# Genus_MainBoard_Dev_v_1_0.net
KiCad netlist of a schematic drawn in EAGLE
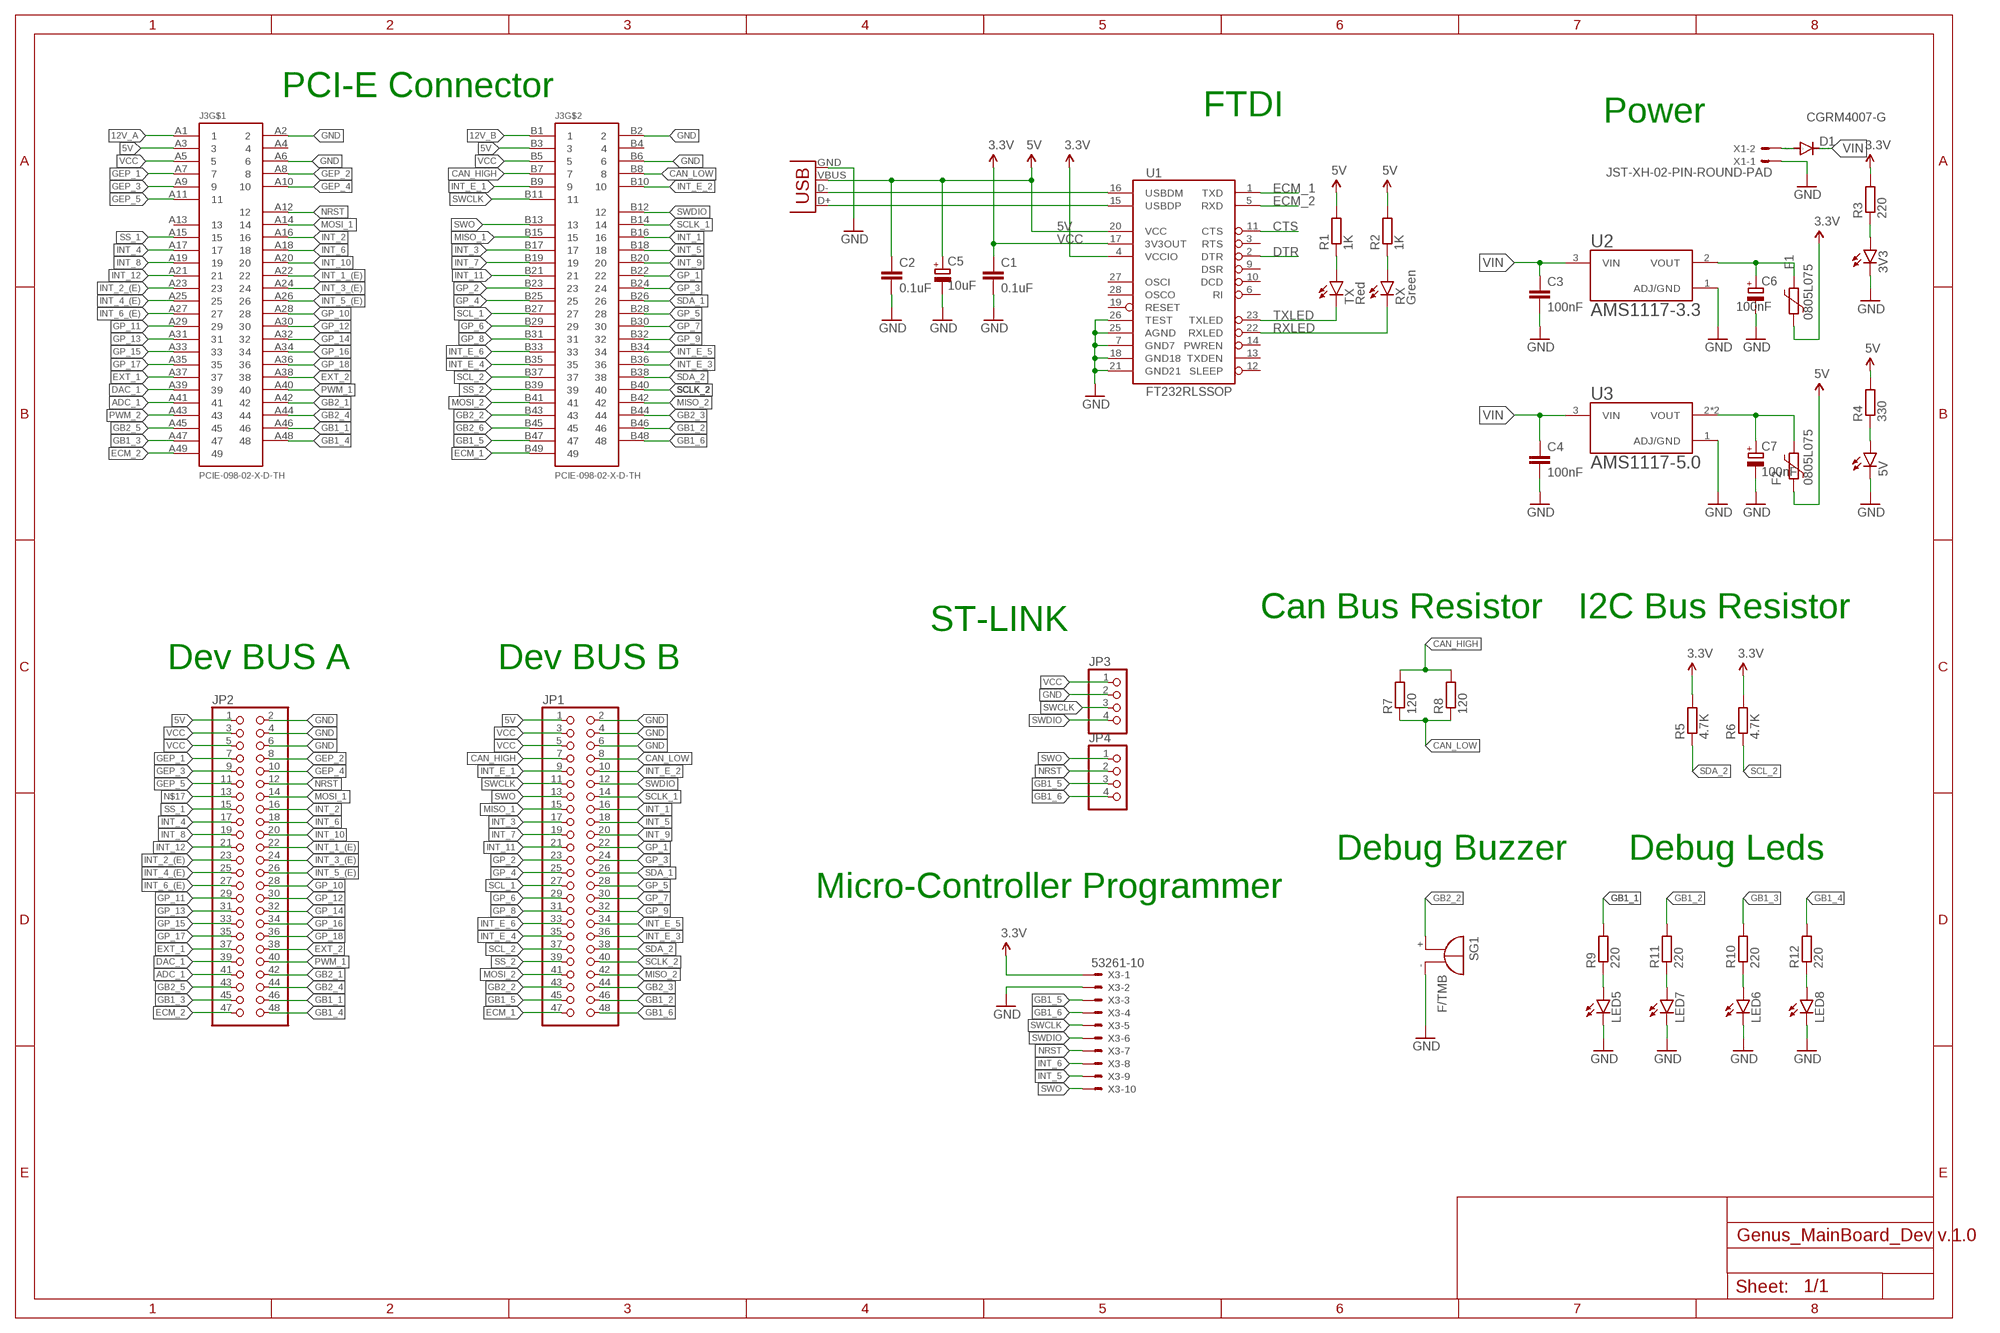
[diagram p0: schematic, sheet 1]

(export (version "E")
  (design (tool "Eeschema 10.0.6"))
  (components
    (comp (ref "3V3")
      (value "LEDCHIPLED_0805")
      (footprint "eagle-import:CHIPLED_0805")
      (libsource (lib "eagle-import") (part "LEDCHIPLED_0805"))
    )
    (comp (ref "5V")
      (value "LEDCHIPLED_0805")
      (footprint "eagle-import:CHIPLED_0805")
      (libsource (lib "eagle-import") (part "LEDCHIPLED_0805"))
    )
    (comp (ref "C1")
      (value "0.1uF")
      (footprint "eagle-import:C0805")
      (libsource (lib "eagle-import") (part "C-EUC0805"))
    )
    (comp (ref "C2")
      (value "0.1uF")
      (footprint "eagle-import:C0805")
      (libsource (lib "eagle-import") (part "C-EUC0805"))
    )
    (comp (ref "C3")
      (value "100nF")
      (footprint "eagle-import:C0805")
      (libsource (lib "eagle-import") (part "C-EUC0805"))
    )
    (comp (ref "C4")
      (value "100nF")
      (footprint "eagle-import:C0805")
      (libsource (lib "eagle-import") (part "C-EUC0805"))
    )
    (comp (ref "C5")
      (value "10uF")
      (footprint "eagle-import:PANASONIC_B")
      (libsource (lib "eagle-import") (part "CPOL-EUB"))
    )
    (comp (ref "C6")
      (value "100nF")
      (footprint "eagle-import:PANASONIC_B")
      (libsource (lib "eagle-import") (part "CPOL-EUB"))
    )
    (comp (ref "C7")
      (value "100nF")
      (footprint "eagle-import:PANASONIC_B")
      (libsource (lib "eagle-import") (part "CPOL-EUB"))
    )
    (comp (ref "D1")
      (value "CGRM4007-G")
      (footprint "eagle-import:SOD-123_MINI-SMA")
      (libsource (lib "eagle-import") (part "CGRM400-G7"))
    )
    (comp (ref "F1")
      (value "0805L075")
      (footprint "eagle-import:0805L")
      (fields (field (name "MF") "Littelfuse"))
      (libsource (lib "eagle-import") (part "?0805L075"))
    )
    (comp (ref "F2")
      (value "0805L075")
      (footprint "eagle-import:0805L")
      (fields (field (name "MF") "Littelfuse"))
      (libsource (lib "eagle-import") (part "?0805L075"))
    )
    (comp (ref "J3")
      (value "PCIE-098-02-X-D-TH")
      (footprint "eagle-import:PCIE-098-02-X-D-TH")
      (fields (field (name "MF") "Samtec") (field (name "MP") "PCIE-098-02-F-D-TH"))
      (libsource (lib "eagle-import") (part "PCIE-098-02-X-D-TH"))
    )
    (comp (ref "JP1")
      (value "PINHD-2X24")
      (footprint "eagle-import:2X24")
      (libsource (lib "eagle-import") (part "PINHD-2X24"))
    )
    (comp (ref "JP2")
      (value "PINHD-2X24")
      (footprint "eagle-import:2X24")
      (libsource (lib "eagle-import") (part "PINHD-2X24"))
    )
    (comp (ref "JP3")
      (value "PINHD-1X4")
      (footprint "eagle-import:1X04")
      (libsource (lib "eagle-import") (part "PINHD-1X4"))
    )
    (comp (ref "JP4")
      (value "PINHD-1X4")
      (footprint "eagle-import:1X04")
      (libsource (lib "eagle-import") (part "PINHD-1X4"))
    )
    (comp (ref "LED5")
      (value "LEDCHIPLED_0805")
      (footprint "eagle-import:CHIPLED_0805")
      (libsource (lib "eagle-import") (part "LEDCHIPLED_0805"))
    )
    (comp (ref "LED6")
      (value "LEDCHIPLED_0805")
      (footprint "eagle-import:CHIPLED_0805")
      (libsource (lib "eagle-import") (part "LEDCHIPLED_0805"))
    )
    (comp (ref "LED7")
      (value "LEDCHIPLED_0805")
      (footprint "eagle-import:CHIPLED_0805")
      (libsource (lib "eagle-import") (part "LEDCHIPLED_0805"))
    )
    (comp (ref "LED8")
      (value "LEDCHIPLED_0805")
      (footprint "eagle-import:CHIPLED_0805")
      (libsource (lib "eagle-import") (part "LEDCHIPLED_0805"))
    )
    (comp (ref "R1")
      (value "1K")
      (footprint "eagle-import:R0805")
      (libsource (lib "eagle-import") (part "R-EU_R0805"))
    )
    (comp (ref "R2")
      (value "1K")
      (footprint "eagle-import:R0805")
      (libsource (lib "eagle-import") (part "R-EU_R0805"))
    )
    (comp (ref "R3")
      (value "220")
      (footprint "eagle-import:R0805")
      (libsource (lib "eagle-import") (part "R-EU_R0805"))
    )
    (comp (ref "R4")
      (value "330")
      (footprint "eagle-import:R0805")
      (libsource (lib "eagle-import") (part "R-EU_R0805"))
    )
    (comp (ref "R5")
      (value "4.7K")
      (footprint "eagle-import:R0805")
      (libsource (lib "eagle-import") (part "R-EU_R0805"))
    )
    (comp (ref "R6")
      (value "4.7K")
      (footprint "eagle-import:R0805")
      (libsource (lib "eagle-import") (part "R-EU_R0805"))
    )
    (comp (ref "R7")
      (value "120")
      (footprint "eagle-import:R0805")
      (libsource (lib "eagle-import") (part "R-EU_R0805"))
    )
    (comp (ref "R8")
      (value "120")
      (footprint "eagle-import:R0805")
      (libsource (lib "eagle-import") (part "R-EU_R0805"))
    )
    (comp (ref "R9")
      (value "220")
      (footprint "eagle-import:R0805")
      (libsource (lib "eagle-import") (part "R-EU_R0805"))
    )
    (comp (ref "R10")
      (value "220")
      (footprint "eagle-import:R0805")
      (libsource (lib "eagle-import") (part "R-EU_R0805"))
    )
    (comp (ref "R11")
      (value "220")
      (footprint "eagle-import:R0805")
      (libsource (lib "eagle-import") (part "R-EU_R0805"))
    )
    (comp (ref "R12")
      (value "220")
      (footprint "eagle-import:R0805")
      (libsource (lib "eagle-import") (part "R-EU_R0805"))
    )
    (comp (ref "RX")
      (value "Green")
      (footprint "eagle-import:CHIPLED_0805")
      (libsource (lib "eagle-import") (part "LEDCHIPLED_0805"))
    )
    (comp (ref "SG1")
      (value "F/TMB")
      (footprint "eagle-import:F_TMB")
      (libsource (lib "eagle-import") (part "F/TMB"))
    )
    (comp (ref "TX")
      (value "Red")
      (footprint "eagle-import:CHIPLED_0805")
      (libsource (lib "eagle-import") (part "LEDCHIPLED_0805"))
    )
    (comp (ref "U1")
      (value "FT232RLSSOP")
      (footprint "eagle-import:SSOP28DB")
      (libsource (lib "eagle-import") (part "FT232RLSSOP"))
    )
    (comp (ref "U2")
      (value "AMS1117-3.3")
      (footprint "eagle-import:SOT229P700X180-4N")
      (fields (field (name "MF") "Advanced Monolithic Systems"))
      (libsource (lib "eagle-import") (part "AMS1117-3.3"))
    )
    (comp (ref "U3")
      (value "AMS1117-5.0")
      (footprint "eagle-import:SOT229P700X180-4N")
      (fields (field (name "MF") "ams"))
      (libsource (lib "eagle-import") (part "AMS1117-5.0"))
    )
    (comp (ref "X1")
      (value "JST-XH-02-PIN-ROUND-PAD")
      (footprint "eagle-import:JST-XH-02-PACKAGE-ROUND-PAD")
      (libsource (lib "eagle-import") (part "JST-XH-02-PIN-ROUND-PAD"))
    )
    (comp (ref "X2")
      (value "USB-SMD-NS")
      (footprint "eagle-import:USB-MINIB-NOSTOP")
      (libsource (lib "eagle-import") (part "USB-SMD-NS"))
    )
    (comp (ref "X3")
      (value "53261-10")
      (footprint "eagle-import:53261-10")
      (fields (field (name "MF") "MOLEX"))
      (libsource (lib "eagle-import") (part "53?-10261"))
    )
  )
  (nets
    (net (code "1") (name "/CTS") (class "Default")
      (node (ref "U1") (pin "11") (pinfunction "CTS_11") (pintype "input"))
    )
    (net (code "2") (name "/DTR") (class "Default")
      (node (ref "U1") (pin "2") (pinfunction "DTR_2") (pintype "output"))
    )
    (net (code "3") (name "/RXLED") (class "Default")
      (node (ref "RX") (pin "C") (pinfunction "C_C") (pintype "passive"))
      (node (ref "U1") (pin "22") (pinfunction "RXLED_22") (pintype "input"))
    )
    (net (code "4") (name "/TXLED") (class "Default")
      (node (ref "TX") (pin "C") (pinfunction "C_C") (pintype "passive"))
      (node (ref "U1") (pin "23") (pinfunction "TXLED_23") (pintype "input"))
    )
    (net (code "5") (name "5V") (class "Default")
      (node (ref "C2") (pin "1") (pinfunction "1_1") (pintype "passive"))
      (node (ref "C5") (pin "+") (pinfunction "+_+") (pintype "passive"))
      (node (ref "F2") (pin "2") (pinfunction "2_2") (pintype "passive"))
      (node (ref "J3") (pin "A3") (pinfunction "3_A3") (pintype "bidirectional"))
      (node (ref "J3") (pin "B3") (pinfunction "3_B3") (pintype "bidirectional"))
      (node (ref "JP1") (pin "1") (pinfunction "1_1") (pintype "passive"))
      (node (ref "JP2") (pin "1") (pinfunction "1_1") (pintype "passive"))
      (node (ref "R1") (pin "2") (pinfunction "2_2") (pintype "passive"))
      (node (ref "R2") (pin "2") (pinfunction "2_2") (pintype "passive"))
      (node (ref "R4") (pin "2") (pinfunction "2_2") (pintype "passive"))
      (node (ref "U1") (pin "20") (pinfunction "VCC_20") (pintype "power_in"))
      (node (ref "X2") (pin "VBUS") (pinfunction "VBUS_VBUS") (pintype "bidirectional"))
    )
    (net (code "6") (name "12V_A") (class "Default")
      (node (ref "J3") (pin "A1") (pinfunction "1_A1") (pintype "bidirectional"))
    )
    (net (code "7") (name "12V_B") (class "Default")
      (node (ref "J3") (pin "B1") (pinfunction "1_B1") (pintype "bidirectional"))
    )
    (net (code "8") (name "ADC_1") (class "Default")
      (node (ref "J3") (pin "A41") (pinfunction "41_A41") (pintype "bidirectional"))
      (node (ref "JP2") (pin "41") (pinfunction "41_41") (pintype "passive"))
    )
    (net (code "9") (name "CAN_HIGH") (class "Default")
      (node (ref "J3") (pin "B7") (pinfunction "7_B7") (pintype "bidirectional"))
      (node (ref "JP1") (pin "7") (pinfunction "7_7") (pintype "passive"))
      (node (ref "R7") (pin "2") (pinfunction "2_2") (pintype "passive"))
      (node (ref "R8") (pin "2") (pinfunction "2_2") (pintype "passive"))
    )
    (net (code "10") (name "CAN_LOW") (class "Default")
      (node (ref "J3") (pin "B8") (pinfunction "8_B8") (pintype "bidirectional"))
      (node (ref "JP1") (pin "8") (pinfunction "8_8") (pintype "passive"))
      (node (ref "R7") (pin "1") (pinfunction "1_1") (pintype "passive"))
      (node (ref "R8") (pin "1") (pinfunction "1_1") (pintype "passive"))
    )
    (net (code "11") (name "DAC_1") (class "Default")
      (node (ref "J3") (pin "A39") (pinfunction "39_A39") (pintype "bidirectional"))
      (node (ref "JP2") (pin "39") (pinfunction "39_39") (pintype "passive"))
    )
    (net (code "12") (name "ECM_1") (class "Default")
      (node (ref "J3") (pin "B49") (pinfunction "49_B49") (pintype "bidirectional"))
      (node (ref "JP1") (pin "47") (pinfunction "47_47") (pintype "passive"))
      (node (ref "U1") (pin "1") (pinfunction "TXD_1") (pintype "output"))
    )
    (net (code "13") (name "ECM_2") (class "Default")
      (node (ref "J3") (pin "A49") (pinfunction "49_A49") (pintype "bidirectional"))
      (node (ref "JP2") (pin "47") (pinfunction "47_47") (pintype "passive"))
      (node (ref "U1") (pin "5") (pinfunction "RXD_5") (pintype "input"))
    )
    (net (code "14") (name "EXT_1") (class "Default")
      (node (ref "J3") (pin "A37") (pinfunction "37_A37") (pintype "bidirectional"))
      (node (ref "JP2") (pin "37") (pinfunction "37_37") (pintype "passive"))
    )
    (net (code "15") (name "EXT_2") (class "Default")
      (node (ref "J3") (pin "A38") (pinfunction "38_A38") (pintype "bidirectional"))
      (node (ref "JP2") (pin "38") (pinfunction "38_38") (pintype "passive"))
    )
    (net (code "16") (name "GB1_1") (class "Default")
      (node (ref "J3") (pin "A46") (pinfunction "46_A46") (pintype "bidirectional"))
      (node (ref "JP2") (pin "46") (pinfunction "46_46") (pintype "passive"))
      (node (ref "R9") (pin "2") (pinfunction "2_2") (pintype "passive"))
    )
    (net (code "17") (name "GB1_2") (class "Default")
      (node (ref "J3") (pin "B46") (pinfunction "46_B46") (pintype "bidirectional"))
      (node (ref "JP1") (pin "46") (pinfunction "46_46") (pintype "passive"))
      (node (ref "R11") (pin "2") (pinfunction "2_2") (pintype "passive"))
    )
    (net (code "18") (name "GB1_3") (class "Default")
      (node (ref "J3") (pin "A47") (pinfunction "47_A47") (pintype "bidirectional"))
      (node (ref "JP2") (pin "45") (pinfunction "45_45") (pintype "passive"))
      (node (ref "R10") (pin "2") (pinfunction "2_2") (pintype "passive"))
    )
    (net (code "19") (name "GB1_4") (class "Default")
      (node (ref "J3") (pin "A48") (pinfunction "48_A48") (pintype "bidirectional"))
      (node (ref "JP2") (pin "48") (pinfunction "48_48") (pintype "passive"))
      (node (ref "R12") (pin "2") (pinfunction "2_2") (pintype "passive"))
    )
    (net (code "20") (name "GB1_5") (class "Default")
      (node (ref "J3") (pin "B47") (pinfunction "47_B47") (pintype "bidirectional"))
      (node (ref "JP1") (pin "45") (pinfunction "45_45") (pintype "passive"))
      (node (ref "JP4") (pin "3") (pinfunction "3_3") (pintype "passive"))
      (node (ref "X3") (pin "3") (pinfunction "S_3") (pintype "passive"))
    )
    (net (code "21") (name "GB1_6") (class "Default")
      (node (ref "J3") (pin "B48") (pinfunction "48_B48") (pintype "bidirectional"))
      (node (ref "JP1") (pin "48") (pinfunction "48_48") (pintype "passive"))
      (node (ref "JP4") (pin "4") (pinfunction "4_4") (pintype "passive"))
      (node (ref "X3") (pin "4") (pinfunction "S_4") (pintype "passive"))
    )
    (net (code "22") (name "GB2_1") (class "Default")
      (node (ref "J3") (pin "A42") (pinfunction "42_A42") (pintype "bidirectional"))
      (node (ref "JP2") (pin "42") (pinfunction "42_42") (pintype "passive"))
    )
    (net (code "23") (name "GB2_2") (class "Default")
      (node (ref "J3") (pin "B43") (pinfunction "43_B43") (pintype "bidirectional"))
      (node (ref "JP1") (pin "43") (pinfunction "43_43") (pintype "passive"))
      (node (ref "SG1") (pin "+") (pinfunction "+_+") (pintype "passive"))
    )
    (net (code "24") (name "GB2_3") (class "Default")
      (node (ref "J3") (pin "B44") (pinfunction "44_B44") (pintype "bidirectional"))
      (node (ref "JP1") (pin "44") (pinfunction "44_44") (pintype "passive"))
    )
    (net (code "25") (name "GB2_4") (class "Default")
      (node (ref "J3") (pin "A44") (pinfunction "44_A44") (pintype "bidirectional"))
      (node (ref "JP2") (pin "44") (pinfunction "44_44") (pintype "passive"))
    )
    (net (code "26") (name "GB2_5") (class "Default")
      (node (ref "J3") (pin "A45") (pinfunction "45_A45") (pintype "bidirectional"))
      (node (ref "JP2") (pin "43") (pinfunction "43_43") (pintype "passive"))
    )
    (net (code "27") (name "GB2_6") (class "Default")
      (node (ref "J3") (pin "B45") (pinfunction "45_B45") (pintype "bidirectional"))
    )
    (net (code "28") (name "GEP_1") (class "Default")
      (node (ref "J3") (pin "A7") (pinfunction "7_A7") (pintype "bidirectional"))
      (node (ref "JP2") (pin "7") (pinfunction "7_7") (pintype "passive"))
    )
    (net (code "29") (name "GEP_2") (class "Default")
      (node (ref "J3") (pin "A8") (pinfunction "8_A8") (pintype "bidirectional"))
      (node (ref "JP2") (pin "8") (pinfunction "8_8") (pintype "passive"))
    )
    (net (code "30") (name "GEP_3") (class "Default")
      (node (ref "J3") (pin "A9") (pinfunction "9_A9") (pintype "bidirectional"))
      (node (ref "JP2") (pin "9") (pinfunction "9_9") (pintype "passive"))
    )
    (net (code "31") (name "GEP_4") (class "Default")
      (node (ref "J3") (pin "A10") (pinfunction "10_A10") (pintype "bidirectional"))
      (node (ref "JP2") (pin "10") (pinfunction "10_10") (pintype "passive"))
    )
    (net (code "32") (name "GEP_5") (class "Default")
      (node (ref "J3") (pin "A11") (pinfunction "11_A11") (pintype "bidirectional"))
      (node (ref "JP2") (pin "11") (pinfunction "11_11") (pintype "passive"))
    )
    (net (code "33") (name "GND") (class "Default")
      (node (ref "3V3") (pin "C") (pinfunction "C_C") (pintype "passive"))
      (node (ref "5V") (pin "C") (pinfunction "C_C") (pintype "passive"))
      (node (ref "C1") (pin "2") (pinfunction "2_2") (pintype "passive"))
      (node (ref "C2") (pin "2") (pinfunction "2_2") (pintype "passive"))
      (node (ref "C3") (pin "2") (pinfunction "2_2") (pintype "passive"))
      (node (ref "C4") (pin "2") (pinfunction "2_2") (pintype "passive"))
      (node (ref "C5") (pin "-") (pinfunction "-_-") (pintype "passive"))
      (node (ref "C6") (pin "-") (pinfunction "-_-") (pintype "passive"))
      (node (ref "C7") (pin "-") (pinfunction "-_-") (pintype "passive"))
      (node (ref "J3") (pin "A2") (pinfunction "2_A2") (pintype "bidirectional"))
      (node (ref "J3") (pin "A6") (pinfunction "6_A6") (pintype "bidirectional"))
      (node (ref "J3") (pin "B2") (pinfunction "2_B2") (pintype "bidirectional"))
      (node (ref "J3") (pin "B6") (pinfunction "6_B6") (pintype "bidirectional"))
      (node (ref "JP1") (pin "2") (pinfunction "2_2") (pintype "passive"))
      (node (ref "JP1") (pin "4") (pinfunction "4_4") (pintype "passive"))
      (node (ref "JP1") (pin "6") (pinfunction "6_6") (pintype "passive"))
      (node (ref "JP2") (pin "2") (pinfunction "2_2") (pintype "passive"))
      (node (ref "JP2") (pin "4") (pinfunction "4_4") (pintype "passive"))
      (node (ref "JP2") (pin "6") (pinfunction "6_6") (pintype "passive"))
      (node (ref "JP3") (pin "2") (pinfunction "2_2") (pintype "passive"))
      (node (ref "LED5") (pin "C") (pinfunction "C_C") (pintype "passive"))
      (node (ref "LED6") (pin "C") (pinfunction "C_C") (pintype "passive"))
      (node (ref "LED7") (pin "C") (pinfunction "C_C") (pintype "passive"))
      (node (ref "LED8") (pin "C") (pinfunction "C_C") (pintype "passive"))
      (node (ref "SG1") (pin "-") (pinfunction "-_-") (pintype "passive"))
      (node (ref "U1") (pin "18") (pinfunction "GND18_18") (pintype "power_in"))
      (node (ref "U1") (pin "21") (pinfunction "GND21_21") (pintype "power_in"))
      (node (ref "U1") (pin "25") (pinfunction "AGND_25") (pintype "power_in"))
      (node (ref "U1") (pin "26") (pinfunction "TEST_26") (pintype "input"))
      (node (ref "U1") (pin "7") (pinfunction "GND7_7") (pintype "power_in"))
      (node (ref "U2") (pin "1") (pinfunction "ADJ/GND_1") (pintype "power_in"))
      (node (ref "U3") (pin "1") (pinfunction "ADJ/GND_1") (pintype "power_in"))
      (node (ref "X1") (pin "1") (pinfunction "S_1") (pintype "passive"))
      (node (ref "X2") (pin "GND") (pinfunction "GND_GND") (pintype "bidirectional"))
      (node (ref "X3") (pin "2") (pinfunction "S_2") (pintype "passive"))
    )
    (net (code "34") (name "GP_1") (class "Default")
      (node (ref "J3") (pin "B22") (pinfunction "22_B22") (pintype "bidirectional"))
      (node (ref "JP1") (pin "22") (pinfunction "22_22") (pintype "passive"))
    )
    (net (code "35") (name "GP_2") (class "Default")
      (node (ref "J3") (pin "B23") (pinfunction "23_B23") (pintype "bidirectional"))
      (node (ref "JP1") (pin "23") (pinfunction "23_23") (pintype "passive"))
    )
    (net (code "36") (name "GP_3") (class "Default")
      (node (ref "J3") (pin "B24") (pinfunction "24_B24") (pintype "bidirectional"))
      (node (ref "JP1") (pin "24") (pinfunction "24_24") (pintype "passive"))
    )
    (net (code "37") (name "GP_4") (class "Default")
      (node (ref "J3") (pin "B25") (pinfunction "25_B25") (pintype "bidirectional"))
      (node (ref "JP1") (pin "25") (pinfunction "25_25") (pintype "passive"))
    )
    (net (code "38") (name "GP_5") (class "Default")
      (node (ref "J3") (pin "B28") (pinfunction "28_B28") (pintype "bidirectional"))
      (node (ref "JP1") (pin "28") (pinfunction "28_28") (pintype "passive"))
    )
    (net (code "39") (name "GP_6") (class "Default")
      (node (ref "J3") (pin "B29") (pinfunction "29_B29") (pintype "bidirectional"))
      (node (ref "JP1") (pin "29") (pinfunction "29_29") (pintype "passive"))
    )
    (net (code "40") (name "GP_7") (class "Default")
      (node (ref "J3") (pin "B30") (pinfunction "30_B30") (pintype "bidirectional"))
      (node (ref "JP1") (pin "30") (pinfunction "30_30") (pintype "passive"))
    )
    (net (code "41") (name "GP_8") (class "Default")
      (node (ref "J3") (pin "B31") (pinfunction "31_B31") (pintype "bidirectional"))
      (node (ref "JP1") (pin "31") (pinfunction "31_31") (pintype "passive"))
    )
    (net (code "42") (name "GP_9") (class "Default")
      (node (ref "J3") (pin "B32") (pinfunction "32_B32") (pintype "bidirectional"))
      (node (ref "JP1") (pin "32") (pinfunction "32_32") (pintype "passive"))
    )
    (net (code "43") (name "GP_10") (class "Default")
      (node (ref "J3") (pin "A28") (pinfunction "28_A28") (pintype "bidirectional"))
      (node (ref "JP2") (pin "28") (pinfunction "28_28") (pintype "passive"))
    )
    (net (code "44") (name "GP_11") (class "Default")
      (node (ref "J3") (pin "A29") (pinfunction "29_A29") (pintype "bidirectional"))
      (node (ref "JP2") (pin "29") (pinfunction "29_29") (pintype "passive"))
    )
    (net (code "45") (name "GP_12") (class "Default")
      (node (ref "J3") (pin "A30") (pinfunction "30_A30") (pintype "bidirectional"))
      (node (ref "JP2") (pin "30") (pinfunction "30_30") (pintype "passive"))
    )
    (net (code "46") (name "GP_13") (class "Default")
      (node (ref "J3") (pin "A31") (pinfunction "31_A31") (pintype "bidirectional"))
      (node (ref "JP2") (pin "31") (pinfunction "31_31") (pintype "passive"))
    )
    (net (code "47") (name "GP_14") (class "Default")
      (node (ref "J3") (pin "A32") (pinfunction "32_A32") (pintype "bidirectional"))
      (node (ref "JP2") (pin "32") (pinfunction "32_32") (pintype "passive"))
    )
    (net (code "48") (name "GP_15") (class "Default")
      (node (ref "J3") (pin "A33") (pinfunction "33_A33") (pintype "bidirectional"))
      (node (ref "JP2") (pin "33") (pinfunction "33_33") (pintype "passive"))
    )
    (net (code "49") (name "GP_16") (class "Default")
      (node (ref "J3") (pin "A34") (pinfunction "34_A34") (pintype "bidirectional"))
      (node (ref "JP2") (pin "34") (pinfunction "34_34") (pintype "passive"))
    )
    (net (code "50") (name "GP_17") (class "Default")
      (node (ref "J3") (pin "A35") (pinfunction "35_A35") (pintype "bidirectional"))
      (node (ref "JP2") (pin "35") (pinfunction "35_35") (pintype "passive"))
    )
    (net (code "51") (name "GP_18") (class "Default")
      (node (ref "J3") (pin "A36") (pinfunction "36_A36") (pintype "bidirectional"))
      (node (ref "JP2") (pin "36") (pinfunction "36_36") (pintype "passive"))
    )
    (net (code "52") (name "INT_1") (class "Default")
      (node (ref "J3") (pin "B16") (pinfunction "16_B16") (pintype "bidirectional"))
      (node (ref "JP1") (pin "16") (pinfunction "16_16") (pintype "passive"))
    )
    (net (code "53") (name "INT_1_(E)") (class "Default")
      (node (ref "J3") (pin "A22") (pinfunction "22_A22") (pintype "bidirectional"))
      (node (ref "JP2") (pin "22") (pinfunction "22_22") (pintype "passive"))
    )
    (net (code "54") (name "INT_2") (class "Default")
      (node (ref "J3") (pin "A16") (pinfunction "16_A16") (pintype "bidirectional"))
      (node (ref "JP2") (pin "16") (pinfunction "16_16") (pintype "passive"))
    )
    (net (code "55") (name "INT_2_(E)") (class "Default")
      (node (ref "J3") (pin "A23") (pinfunction "23_A23") (pintype "bidirectional"))
      (node (ref "JP2") (pin "23") (pinfunction "23_23") (pintype "passive"))
    )
    (net (code "56") (name "INT_3") (class "Default")
      (node (ref "J3") (pin "B17") (pinfunction "17_B17") (pintype "bidirectional"))
      (node (ref "JP1") (pin "17") (pinfunction "17_17") (pintype "passive"))
    )
    (net (code "57") (name "INT_3_(E)") (class "Default")
      (node (ref "J3") (pin "A24") (pinfunction "24_A24") (pintype "bidirectional"))
      (node (ref "JP2") (pin "24") (pinfunction "24_24") (pintype "passive"))
    )
    (net (code "58") (name "INT_4") (class "Default")
      (node (ref "J3") (pin "A17") (pinfunction "17_A17") (pintype "bidirectional"))
      (node (ref "JP2") (pin "17") (pinfunction "17_17") (pintype "passive"))
    )
    (net (code "59") (name "INT_4_(E)") (class "Default")
      (node (ref "J3") (pin "A25") (pinfunction "25_A25") (pintype "bidirectional"))
      (node (ref "JP2") (pin "25") (pinfunction "25_25") (pintype "passive"))
    )
    (net (code "60") (name "INT_5") (class "Default")
      (node (ref "J3") (pin "B18") (pinfunction "18_B18") (pintype "bidirectional"))
      (node (ref "JP1") (pin "18") (pinfunction "18_18") (pintype "passive"))
      (node (ref "X3") (pin "9") (pinfunction "S_9") (pintype "passive"))
    )
    (net (code "61") (name "INT_5_(E)") (class "Default")
      (node (ref "J3") (pin "A26") (pinfunction "26_A26") (pintype "bidirectional"))
      (node (ref "JP2") (pin "26") (pinfunction "26_26") (pintype "passive"))
    )
    (net (code "62") (name "INT_6") (class "Default")
      (node (ref "J3") (pin "A18") (pinfunction "18_A18") (pintype "bidirectional"))
      (node (ref "JP2") (pin "18") (pinfunction "18_18") (pintype "passive"))
      (node (ref "X3") (pin "8") (pinfunction "S_8") (pintype "passive"))
    )
    (net (code "63") (name "INT_6_(E)") (class "Default")
      (node (ref "J3") (pin "A27") (pinfunction "27_A27") (pintype "bidirectional"))
      (node (ref "JP2") (pin "27") (pinfunction "27_27") (pintype "passive"))
    )
    (net (code "64") (name "INT_7") (class "Default")
      (node (ref "J3") (pin "B19") (pinfunction "19_B19") (pintype "bidirectional"))
      (node (ref "JP1") (pin "19") (pinfunction "19_19") (pintype "passive"))
    )
    (net (code "65") (name "INT_8") (class "Default")
      (node (ref "J3") (pin "A19") (pinfunction "19_A19") (pintype "bidirectional"))
      (node (ref "JP2") (pin "19") (pinfunction "19_19") (pintype "passive"))
    )
    (net (code "66") (name "INT_9") (class "Default")
      (node (ref "J3") (pin "B20") (pinfunction "20_B20") (pintype "bidirectional"))
      (node (ref "JP1") (pin "20") (pinfunction "20_20") (pintype "passive"))
    )
    (net (code "67") (name "INT_10") (class "Default")
      (node (ref "J3") (pin "A20") (pinfunction "20_A20") (pintype "bidirectional"))
      (node (ref "JP2") (pin "20") (pinfunction "20_20") (pintype "passive"))
    )
    (net (code "68") (name "INT_11") (class "Default")
      (node (ref "J3") (pin "B21") (pinfunction "21_B21") (pintype "bidirectional"))
      (node (ref "JP1") (pin "21") (pinfunction "21_21") (pintype "passive"))
    )
    (net (code "69") (name "INT_12") (class "Default")
      (node (ref "J3") (pin "A21") (pinfunction "21_A21") (pintype "bidirectional"))
      (node (ref "JP2") (pin "21") (pinfunction "21_21") (pintype "passive"))
    )
    (net (code "70") (name "INT_E_1") (class "Default")
      (node (ref "J3") (pin "B9") (pinfunction "9_B9") (pintype "bidirectional"))
      (node (ref "JP1") (pin "9") (pinfunction "9_9") (pintype "passive"))
    )
    (net (code "71") (name "INT_E_2") (class "Default")
      (node (ref "J3") (pin "B10") (pinfunction "10_B10") (pintype "bidirectional"))
      (node (ref "JP1") (pin "10") (pinfunction "10_10") (pintype "passive"))
    )
    (net (code "72") (name "INT_E_3") (class "Default")
      (node (ref "J3") (pin "B36") (pinfunction "36_B36") (pintype "bidirectional"))
      (node (ref "JP1") (pin "36") (pinfunction "36_36") (pintype "passive"))
    )
    (net (code "73") (name "INT_E_4") (class "Default")
      (node (ref "J3") (pin "B35") (pinfunction "35_B35") (pintype "bidirectional"))
      (node (ref "JP1") (pin "35") (pinfunction "35_35") (pintype "passive"))
    )
    (net (code "74") (name "INT_E_5") (class "Default")
      (node (ref "J3") (pin "B34") (pinfunction "34_B34") (pintype "bidirectional"))
      (node (ref "JP1") (pin "34") (pinfunction "34_34") (pintype "passive"))
    )
    (net (code "75") (name "INT_E_6") (class "Default")
      (node (ref "J3") (pin "B33") (pinfunction "33_B33") (pintype "bidirectional"))
      (node (ref "JP1") (pin "33") (pinfunction "33_33") (pintype "passive"))
    )
    (net (code "76") (name "MISO_1") (class "Default")
      (node (ref "J3") (pin "B15") (pinfunction "15_B15") (pintype "bidirectional"))
      (node (ref "JP1") (pin "15") (pinfunction "15_15") (pintype "passive"))
    )
    (net (code "77") (name "MISO_2") (class "Default")
      (node (ref "J3") (pin "B42") (pinfunction "42_B42") (pintype "bidirectional"))
      (node (ref "JP1") (pin "42") (pinfunction "42_42") (pintype "passive"))
    )
    (net (code "78") (name "MOSI_1") (class "Default")
      (node (ref "J3") (pin "A14") (pinfunction "14_A14") (pintype "bidirectional"))
      (node (ref "JP2") (pin "14") (pinfunction "14_14") (pintype "passive"))
    )
    (net (code "79") (name "MOSI_2") (class "Default")
      (node (ref "J3") (pin "B41") (pinfunction "41_B41") (pintype "bidirectional"))
      (node (ref "JP1") (pin "41") (pinfunction "41_41") (pintype "passive"))
    )
    (net (code "80") (name "N$17") (class "Default")
      (node (ref "JP2") (pin "13") (pinfunction "13_13") (pintype "passive"))
    )
    (net (code "81") (name "NRST") (class "Default")
      (node (ref "J3") (pin "A12") (pinfunction "12_A12") (pintype "bidirectional"))
      (node (ref "JP2") (pin "12") (pinfunction "12_12") (pintype "passive"))
      (node (ref "JP4") (pin "2") (pinfunction "2_2") (pintype "passive"))
      (node (ref "X3") (pin "7") (pinfunction "S_7") (pintype "passive"))
    )
    (net (code "82") (name "Net-(3V3-PadA)") (class "Default")
      (node (ref "3V3") (pin "A") (pinfunction "A_A") (pintype "passive"))
      (node (ref "R3") (pin "1") (pinfunction "1_1") (pintype "passive"))
    )
    (net (code "83") (name "Net-(5V-PadA)") (class "Default")
      (node (ref "5V") (pin "A") (pinfunction "A_A") (pintype "passive"))
      (node (ref "R4") (pin "1") (pinfunction "1_1") (pintype "passive"))
    )
    (net (code "84") (name "Net-(C7-Pad+)") (class "Default")
      (node (ref "C7") (pin "+") (pinfunction "+_+") (pintype "passive"))
      (node (ref "F2") (pin "1") (pinfunction "1_1") (pintype "passive"))
      (node (ref "U3") (pin "2") (pinfunction "VOUT_2") (pintype "output"))
      (node (ref "U3") (pin "4") (pinfunction "VOUT_4") (pintype "output"))
    )
    (net (code "85") (name "Net-(LED5-PadA)") (class "Default")
      (node (ref "LED5") (pin "A") (pinfunction "A_A") (pintype "passive"))
      (node (ref "R9") (pin "1") (pinfunction "1_1") (pintype "passive"))
    )
    (net (code "86") (name "Net-(LED6-PadA)") (class "Default")
      (node (ref "LED6") (pin "A") (pinfunction "A_A") (pintype "passive"))
      (node (ref "R10") (pin "1") (pinfunction "1_1") (pintype "passive"))
    )
    (net (code "87") (name "Net-(LED7-PadA)") (class "Default")
      (node (ref "LED7") (pin "A") (pinfunction "A_A") (pintype "passive"))
      (node (ref "R11") (pin "1") (pinfunction "1_1") (pintype "passive"))
    )
    (net (code "88") (name "Net-(LED8-PadA)") (class "Default")
      (node (ref "LED8") (pin "A") (pinfunction "A_A") (pintype "passive"))
      (node (ref "R12") (pin "1") (pinfunction "1_1") (pintype "passive"))
    )
    (net (code "89") (name "Net-(R1-Pad1)") (class "Default")
      (node (ref "R1") (pin "1") (pinfunction "1_1") (pintype "passive"))
      (node (ref "TX") (pin "A") (pinfunction "A_A") (pintype "passive"))
    )
    (net (code "90") (name "Net-(R2-Pad1)") (class "Default")
      (node (ref "R2") (pin "1") (pinfunction "1_1") (pintype "passive"))
      (node (ref "RX") (pin "A") (pinfunction "A_A") (pintype "passive"))
    )
    (net (code "91") (name "Net-(U1-USBDM)") (class "Default")
      (node (ref "U1") (pin "16") (pinfunction "USBDM_16") (pintype "bidirectional"))
      (node (ref "X2") (pin "D-") (pinfunction "D-_D-") (pintype "bidirectional"))
    )
    (net (code "92") (name "Net-(U1-USBDP)") (class "Default")
      (node (ref "U1") (pin "15") (pinfunction "USBDP_15") (pintype "bidirectional"))
      (node (ref "X2") (pin "D+") (pinfunction "D+_D+") (pintype "bidirectional"))
    )
    (net (code "93") (name "Net-(U2-VOUT)") (class "Default")
      (node (ref "C6") (pin "+") (pinfunction "+_+") (pintype "passive"))
      (node (ref "F1") (pin "1") (pinfunction "1_1") (pintype "passive"))
      (node (ref "U2") (pin "2") (pinfunction "VOUT_2") (pintype "output"))
    )
    (net (code "94") (name "Net-(X1B-S)") (class "Default")
      (node (ref "D1") (pin "A") (pinfunction "A_A") (pintype "passive"))
      (node (ref "X1") (pin "2") (pinfunction "S_2") (pintype "passive"))
    )
    (net (code "95") (name "PWM_1") (class "Default")
      (node (ref "J3") (pin "A40") (pinfunction "40_A40") (pintype "bidirectional"))
      (node (ref "JP2") (pin "40") (pinfunction "40_40") (pintype "passive"))
    )
    (net (code "96") (name "PWM_2") (class "Default")
      (node (ref "J3") (pin "A43") (pinfunction "43_A43") (pintype "bidirectional"))
    )
    (net (code "97") (name "SCLK_1") (class "Default")
      (node (ref "J3") (pin "B14") (pinfunction "14_B14") (pintype "bidirectional"))
      (node (ref "JP1") (pin "14") (pinfunction "14_14") (pintype "passive"))
    )
    (net (code "98") (name "SCLK_2") (class "Default")
      (node (ref "J3") (pin "B40") (pinfunction "40_B40") (pintype "bidirectional"))
      (node (ref "JP1") (pin "40") (pinfunction "40_40") (pintype "passive"))
    )
    (net (code "99") (name "SCL_1") (class "Default")
      (node (ref "J3") (pin "B27") (pinfunction "27_B27") (pintype "bidirectional"))
      (node (ref "JP1") (pin "27") (pinfunction "27_27") (pintype "passive"))
    )
    (net (code "100") (name "SCL_2") (class "Default")
      (node (ref "J3") (pin "B37") (pinfunction "37_B37") (pintype "bidirectional"))
      (node (ref "JP1") (pin "37") (pinfunction "37_37") (pintype "passive"))
      (node (ref "R6") (pin "1") (pinfunction "1_1") (pintype "passive"))
    )
    (net (code "101") (name "SDA_1") (class "Default")
      (node (ref "J3") (pin "B26") (pinfunction "26_B26") (pintype "bidirectional"))
      (node (ref "JP1") (pin "26") (pinfunction "26_26") (pintype "passive"))
    )
    (net (code "102") (name "SDA_2") (class "Default")
      (node (ref "J3") (pin "B38") (pinfunction "38_B38") (pintype "bidirectional"))
      (node (ref "JP1") (pin "38") (pinfunction "38_38") (pintype "passive"))
      (node (ref "R5") (pin "1") (pinfunction "1_1") (pintype "passive"))
    )
    (net (code "103") (name "SS_1") (class "Default")
      (node (ref "J3") (pin "A15") (pinfunction "15_A15") (pintype "bidirectional"))
      (node (ref "JP2") (pin "15") (pinfunction "15_15") (pintype "passive"))
    )
    (net (code "104") (name "SS_2") (class "Default")
      (node (ref "J3") (pin "B39") (pinfunction "39_B39") (pintype "bidirectional"))
      (node (ref "JP1") (pin "39") (pinfunction "39_39") (pintype "passive"))
    )
    (net (code "105") (name "SWCLK") (class "Default")
      (node (ref "J3") (pin "B11") (pinfunction "11_B11") (pintype "bidirectional"))
      (node (ref "JP1") (pin "11") (pinfunction "11_11") (pintype "passive"))
      (node (ref "JP3") (pin "3") (pinfunction "3_3") (pintype "passive"))
      (node (ref "X3") (pin "5") (pinfunction "S_5") (pintype "passive"))
    )
    (net (code "106") (name "SWDIO") (class "Default")
      (node (ref "J3") (pin "B12") (pinfunction "12_B12") (pintype "bidirectional"))
      (node (ref "JP1") (pin "12") (pinfunction "12_12") (pintype "passive"))
      (node (ref "JP3") (pin "4") (pinfunction "4_4") (pintype "passive"))
      (node (ref "X3") (pin "6") (pinfunction "S_6") (pintype "passive"))
    )
    (net (code "107") (name "SWO") (class "Default")
      (node (ref "J3") (pin "B13") (pinfunction "13_B13") (pintype "bidirectional"))
      (node (ref "JP1") (pin "13") (pinfunction "13_13") (pintype "passive"))
      (node (ref "JP4") (pin "1") (pinfunction "1_1") (pintype "passive"))
      (node (ref "X3") (pin "10") (pinfunction "S_10") (pintype "passive"))
    )
    (net (code "108") (name "VCC") (class "Default")
      (node (ref "C1") (pin "1") (pinfunction "1_1") (pintype "passive"))
      (node (ref "F1") (pin "2") (pinfunction "2_2") (pintype "passive"))
      (node (ref "J3") (pin "A5") (pinfunction "5_A5") (pintype "bidirectional"))
      (node (ref "J3") (pin "B5") (pinfunction "5_B5") (pintype "bidirectional"))
      (node (ref "JP1") (pin "3") (pinfunction "3_3") (pintype "passive"))
      (node (ref "JP1") (pin "5") (pinfunction "5_5") (pintype "passive"))
      (node (ref "JP2") (pin "3") (pinfunction "3_3") (pintype "passive"))
      (node (ref "JP2") (pin "5") (pinfunction "5_5") (pintype "passive"))
      (node (ref "JP3") (pin "1") (pinfunction "1_1") (pintype "passive"))
      (node (ref "R3") (pin "2") (pinfunction "2_2") (pintype "passive"))
      (node (ref "R5") (pin "2") (pinfunction "2_2") (pintype "passive"))
      (node (ref "R6") (pin "2") (pinfunction "2_2") (pintype "passive"))
      (node (ref "U1") (pin "17") (pinfunction "3V3OUT_17") (pintype "output"))
      (node (ref "U1") (pin "4") (pinfunction "VCCIO_4") (pintype "power_in"))
      (node (ref "X3") (pin "1") (pinfunction "S_1") (pintype "passive"))
    )
    (net (code "109") (name "VIN") (class "Default")
      (node (ref "C3") (pin "1") (pinfunction "1_1") (pintype "passive"))
      (node (ref "C4") (pin "1") (pinfunction "1_1") (pintype "passive"))
      (node (ref "D1") (pin "C") (pinfunction "C_C") (pintype "passive"))
      (node (ref "U2") (pin "3") (pinfunction "VIN_3") (pintype "input"))
      (node (ref "U3") (pin "3") (pinfunction "VIN_3") (pintype "input"))
    )
    (net (code "110") (name "unconnected-(J3A-4-PadA4)") (class "Default")
      (node (ref "J3") (pin "A4") (pinfunction "4_A4") (pintype "bidirectional"))
    )
    (net (code "111") (name "unconnected-(J3A-13-PadA13)") (class "Default")
      (node (ref "J3") (pin "A13") (pinfunction "13_A13") (pintype "bidirectional"))
    )
    (net (code "112") (name "unconnected-(J3B-4-PadB4)") (class "Default")
      (node (ref "J3") (pin "B4") (pinfunction "4_B4") (pintype "bidirectional"))
    )
    (net (code "113") (name "unconnected-(U1-DCD-Pad10)") (class "Default")
      (node (ref "U1") (pin "10") (pinfunction "DCD_10") (pintype "input"))
    )
    (net (code "114") (name "unconnected-(U1-DSR-Pad9)") (class "Default")
      (node (ref "U1") (pin "9") (pinfunction "DSR_9") (pintype "input"))
    )
    (net (code "115") (name "unconnected-(U1-OSCI-Pad27)") (class "Default")
      (node (ref "U1") (pin "27") (pinfunction "OSCI_27") (pintype "input"))
    )
    (net (code "116") (name "unconnected-(U1-OSCO-Pad28)") (class "Default")
      (node (ref "U1") (pin "28") (pinfunction "OSCO_28") (pintype "output"))
    )
    (net (code "117") (name "unconnected-(U1-PWREN-Pad14)") (class "Default")
      (node (ref "U1") (pin "14") (pinfunction "PWREN_14") (pintype "input"))
    )
    (net (code "118") (name "unconnected-(U1-RESET-Pad19)") (class "Default")
      (node (ref "U1") (pin "19") (pinfunction "RESET_19") (pintype "input"))
    )
    (net (code "119") (name "unconnected-(U1-RI-Pad6)") (class "Default")
      (node (ref "U1") (pin "6") (pinfunction "RI_6") (pintype "input"))
    )
    (net (code "120") (name "unconnected-(U1-RTS-Pad3)") (class "Default")
      (node (ref "U1") (pin "3") (pinfunction "RTS_3") (pintype "output"))
    )
    (net (code "121") (name "unconnected-(U1-SLEEP-Pad12)") (class "Default")
      (node (ref "U1") (pin "12") (pinfunction "SLEEP_12") (pintype "input"))
    )
    (net (code "122") (name "unconnected-(U1-TXDEN-Pad13)") (class "Default")
      (node (ref "U1") (pin "13") (pinfunction "TXDEN_13") (pintype "input"))
    )
  )
)
